# Deadtime_logic.net
KiCad netlist of a schematic drawn in Altium Designer
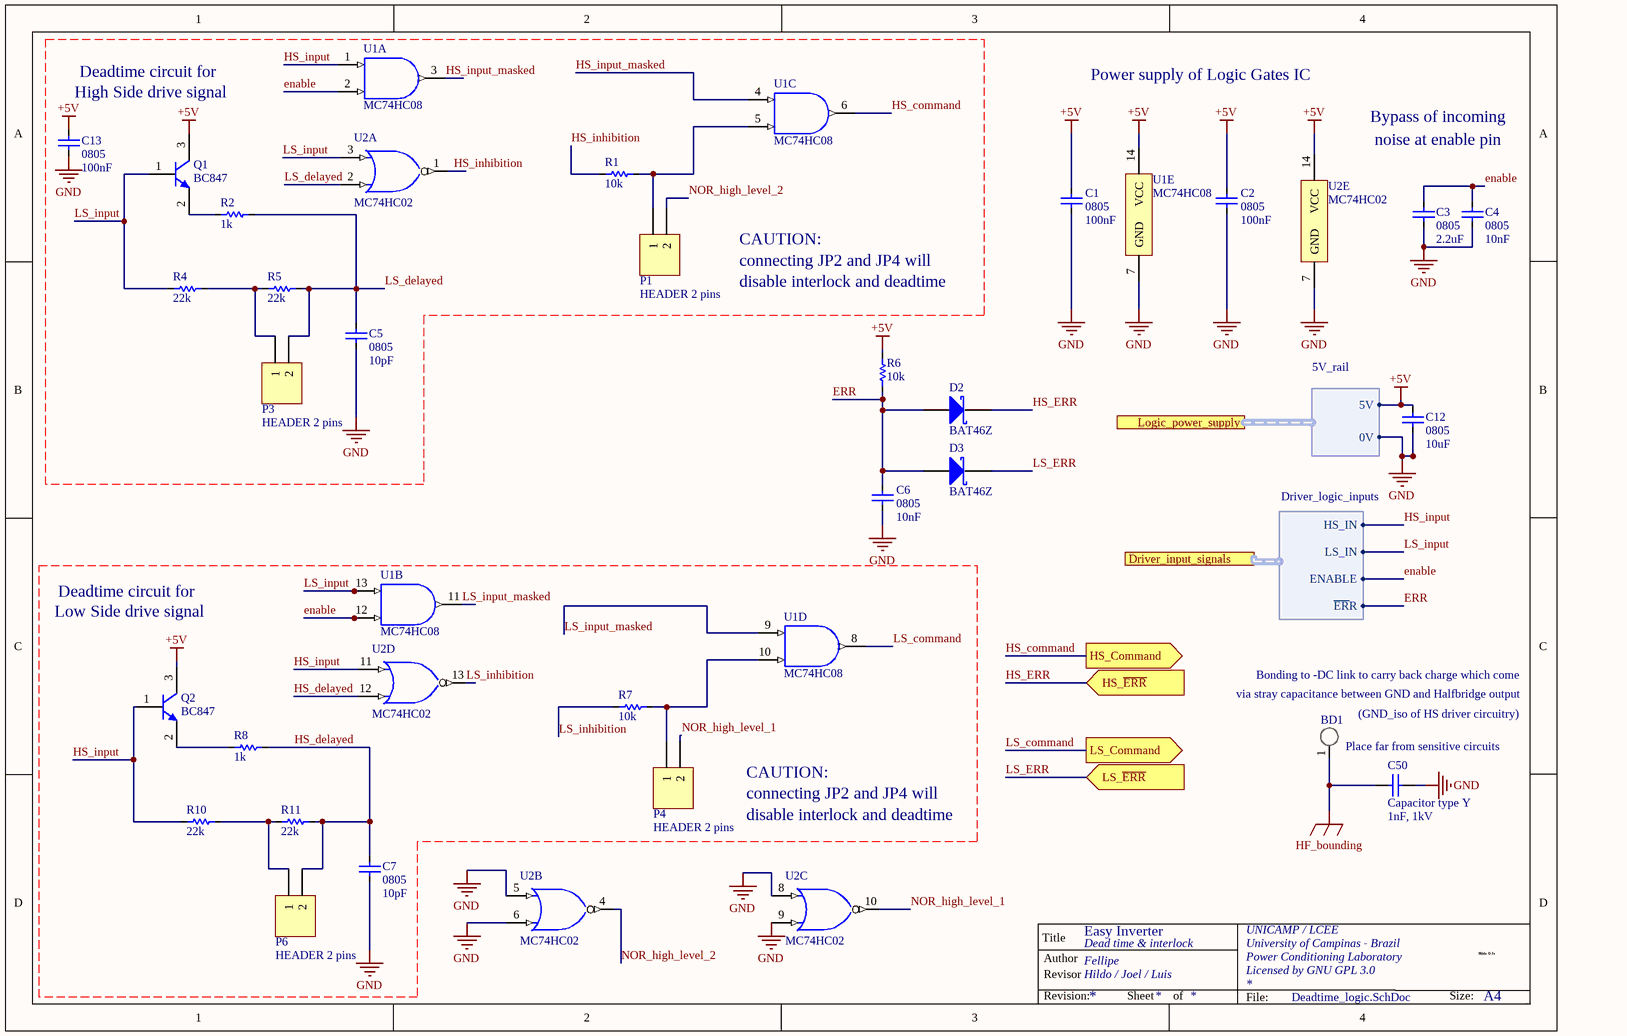
[diagram p0: Deadtime_logic.SchDoc]

(export (version "E")
  (design (tool "Eeschema 10.0.6"))
  (components
    (comp (ref "BD1")
      (value "Place far from sensitive circuits")
      (footprint "Bonding_pad")
      (libsource (lib "EdgeInverter_library") (part "Bonding_pad"))
    )
    (comp (ref "C1")
      (value "0805")
      (footprint "Capacitor 0805")
      (description "SMD ceramic capacitor 0805")
      (fields (field (name "ALTIUM_VALUE") "100nF"))
      (libsource (lib "EdgeInverter_library") (part "Capacitor 0805"))
    )
    (comp (ref "C2")
      (value "0805")
      (footprint "Capacitor 0805")
      (description "SMD ceramic capacitor 0805")
      (fields (field (name "ALTIUM_VALUE") "100nF"))
      (libsource (lib "EdgeInverter_library") (part "Capacitor 0805"))
    )
    (comp (ref "C3")
      (value "0805")
      (footprint "Capacitor 0805")
      (description "SMD ceramic capacitor 0805")
      (fields (field (name "ALTIUM_VALUE") "2.2uF"))
      (libsource (lib "EdgeInverter_library") (part "Capacitor 0805"))
    )
    (comp (ref "C4")
      (value "0805")
      (footprint "Capacitor 0805")
      (description "SMD ceramic capacitor 0805")
      (fields (field (name "ALTIUM_VALUE") "10nF"))
      (libsource (lib "EdgeInverter_library") (part "Capacitor 0805"))
    )
    (comp (ref "C5")
      (value "0805")
      (footprint "Capacitor 0805")
      (description "SMD ceramic capacitor 0805")
      (fields (field (name "ALTIUM_VALUE") "10pF"))
      (libsource (lib "EdgeInverter_library") (part "Capacitor 0805"))
    )
    (comp (ref "C6")
      (value "0805")
      (footprint "Capacitor 0805")
      (description "SMD ceramic capacitor 0805")
      (fields (field (name "ALTIUM_VALUE") "10nF"))
      (libsource (lib "EdgeInverter_library") (part "Capacitor 0805"))
    )
    (comp (ref "C7")
      (value "0805")
      (footprint "Capacitor 0805")
      (description "SMD ceramic capacitor 0805")
      (fields (field (name "ALTIUM_VALUE") "10pF"))
      (libsource (lib "EdgeInverter_library") (part "Capacitor 0805"))
    )
    (comp (ref "C12")
      (value "0805")
      (footprint "Capacitor 0805")
      (description "SMD ceramic capacitor 0805")
      (fields (field (name "ALTIUM_VALUE") "10uF"))
      (libsource (lib "EdgeInverter_library") (part "Capacitor 0805"))
    )
    (comp (ref "C13")
      (value "0805")
      (footprint "Capacitor 0805")
      (description "SMD ceramic capacitor 0805")
      (fields (field (name "ALTIUM_VALUE") "100nF"))
      (libsource (lib "EdgeInverter_library") (part "Capacitor 0805"))
    )
    (comp (ref "C50")
      (value "Capacitor type Y")
      (footprint "CAPACITOR 1812")
      (description "High Voltage Capacitor to filter EMC from heatsink")
      (fields (field (name "ALTIUM_VALUE") "1nF, 1kV"))
      (libsource (lib "EdgeInverter_library") (part "Y Capacitor"))
    )
    (comp (ref "D2")
      (value "BAT46Z")
      (footprint "SOD 123")
      (description "DIODE SCHOTTKY 100V 150MA SOD123")
      (libsource (lib "EdgeInverter_library") (part "BAT46Z"))
    )
    (comp (ref "D3")
      (value "BAT46Z")
      (footprint "SOD 123")
      (description "DIODE SCHOTTKY 100V 150MA SOD123")
      (libsource (lib "EdgeInverter_library") (part "BAT46Z"))
    )
    (comp (ref "P1")
      (value "HEADER 2 pins")
      (footprint "HDR1X2 - Jumper")
      (description "Header 2.54mm 2 pins")
      (libsource (lib "EdgeInverter_library") (part "HEADER 2 pins"))
    )
    (comp (ref "P3")
      (value "HEADER 2 pins")
      (footprint "HDR1X2 - Jumper")
      (description "Header 2.54mm 2 pins")
      (libsource (lib "EdgeInverter_library") (part "HEADER 2 pins"))
    )
    (comp (ref "P4")
      (value "HEADER 2 pins")
      (footprint "HDR1X2 - Jumper")
      (description "Header 2.54mm 2 pins")
      (libsource (lib "EdgeInverter_library") (part "HEADER 2 pins"))
    )
    (comp (ref "P6")
      (value "HEADER 2 pins")
      (footprint "HDR1X2 - Jumper")
      (description "Header 2.54mm 2 pins")
      (libsource (lib "EdgeInverter_library") (part "HEADER 2 pins"))
    )
    (comp (ref "Q1")
      (value "BC847")
      (footprint "SOT 23")
      (description "General Purpose Transistor, NPN Silicon, 3-Pin SOT-23, Pb-Free, Tape and Reel")
      (libsource (lib "EdgeInverter_library") (part "BC847BLT1G"))
    )
    (comp (ref "Q2")
      (value "BC847")
      (footprint "SOT 23")
      (description "General Purpose Transistor, NPN Silicon, 3-Pin SOT-23, Pb-Free, Tape and Reel")
      (libsource (lib "EdgeInverter_library") (part "BC847BLT1G"))
    )
    (comp (ref "R1")
      (value "10k")
      (footprint "Resistor 0805")
      (description "SMD resistor 0805")
      (fields (field (name "Comment") "Resistor 0805"))
      (libsource (lib "EdgeInverter_library") (part "Resistor 0805"))
    )
    (comp (ref "R2")
      (value "1k")
      (footprint "Resistor 0805")
      (description "SMD resistor 0805")
      (fields (field (name "Comment") "Resistor 0805"))
      (libsource (lib "EdgeInverter_library") (part "Resistor 0805"))
    )
    (comp (ref "R4")
      (value "22k")
      (footprint "Resistor 0805")
      (description "SMD resistor 0805")
      (fields (field (name "Comment") "Resistor 0805"))
      (libsource (lib "EdgeInverter_library") (part "Resistor 0805"))
    )
    (comp (ref "R5")
      (value "22k")
      (footprint "Resistor 0805")
      (description "SMD resistor 0805")
      (fields (field (name "Comment") "Resistor 0805"))
      (libsource (lib "EdgeInverter_library") (part "Resistor 0805"))
    )
    (comp (ref "R6")
      (value "10k")
      (footprint "Resistor 0805")
      (description "SMD resistor 0805")
      (fields (field (name "Comment") "Resistor 0805"))
      (libsource (lib "EdgeInverter_library") (part "Resistor 0805"))
    )
    (comp (ref "R7")
      (value "10k")
      (footprint "Resistor 0805")
      (description "SMD resistor 0805")
      (fields (field (name "Comment") "Resistor 0805"))
      (libsource (lib "EdgeInverter_library") (part "Resistor 0805"))
    )
    (comp (ref "R8")
      (value "1k")
      (footprint "Resistor 0805")
      (description "SMD resistor 0805")
      (fields (field (name "Comment") "Resistor 0805"))
      (libsource (lib "EdgeInverter_library") (part "Resistor 0805"))
    )
    (comp (ref "R10")
      (value "22k")
      (footprint "Resistor 0805")
      (description "SMD resistor 0805")
      (fields (field (name "Comment") "Resistor 0805"))
      (libsource (lib "EdgeInverter_library") (part "Resistor 0805"))
    )
    (comp (ref "R11")
      (value "22k")
      (footprint "Resistor 0805")
      (description "SMD resistor 0805")
      (fields (field (name "Comment") "Resistor 0805"))
      (libsource (lib "EdgeInverter_library") (part "Resistor 0805"))
    )
    (comp (ref "U1")
      (value "MC74HC08")
      (footprint "SOIC 14")
      (description "Quadruple 2-Input Positive-AND Gates")
      (fields (field (name "Comment") "MC74HC08ADG"))
      (libsource (lib "") (part "MC74HC08ADG_2"))
    )
    (comp (ref "U2")
      (value "MC74HC02")
      (footprint "SOIC 14")
      (description "Logic Quad 2-Input NOR Gates")
      (fields (field (name "Comment") "MC74HC02ADG"))
      (libsource (lib "") (part "MC74HC02ADG_2"))
    )
  )
  (nets
    (net (code "3") (name "+5V") (class "Default")
      (node (ref "C1") (pin "1") (pinfunction "1_1") (pintype "passive"))
      (node (ref "C12") (pin "1") (pinfunction "1_1") (pintype "passive"))
      (node (ref "C13") (pin "1") (pinfunction "1_1") (pintype "passive"))
      (node (ref "C2") (pin "1") (pinfunction "1_1") (pintype "passive"))
      (node (ref "Q1") (pin "3") (pinfunction "C_3") (pintype "passive"))
      (node (ref "Q2") (pin "3") (pinfunction "C_3") (pintype "passive"))
      (node (ref "R6") (pin "2") (pinfunction "2_2") (pintype "passive"))
      (node (ref "U1") (pin "14") (pinfunction "VCC_14") (pintype "power_in"))
      (node (ref "U2") (pin "14") (pinfunction "VCC_14") (pintype "power_in"))
    )
    (net (code "4") (name "/ERR") (class "Default")
      (node (ref "C6") (pin "1") (pinfunction "1_1") (pintype "passive"))
      (node (ref "D2") (pin "1") (pinfunction "A_1") (pintype "passive"))
      (node (ref "D3") (pin "1") (pinfunction "A_1") (pintype "passive"))
      (node (ref "R6") (pin "1") (pinfunction "1_1") (pintype "passive"))
    )
    (net (code "5") (name "/HS_ERR") (class "Default")
      (node (ref "D2") (pin "2") (pinfunction "K_2") (pintype "passive"))
    )
    (net (code "6") (name "/HS_command") (class "Default")
      (node (ref "U1") (pin "6") (pinfunction "2Y_6") (pintype "output"))
    )
    (net (code "7") (name "/HS_delayed") (class "Default")
      (node (ref "C7") (pin "1") (pinfunction "1_1") (pintype "passive"))
      (node (ref "P6") (pin "2") (pinfunction "2_2") (pintype "passive"))
      (node (ref "R11") (pin "2") (pinfunction "2_2") (pintype "passive"))
      (node (ref "R8") (pin "2") (pinfunction "2_2") (pintype "passive"))
      (node (ref "U2") (pin "12") (pinfunction "4B_12") (pintype "input"))
    )
    (net (code "8") (name "/HS_inhibition") (class "Default")
      (node (ref "R1") (pin "1") (pinfunction "1_1") (pintype "passive"))
      (node (ref "U2") (pin "1") (pinfunction "1Y_1") (pintype "output"))
    )
    (net (code "9") (name "/HS_input") (class "Default")
      (node (ref "Q2") (pin "1") (pinfunction "B_1") (pintype "passive"))
      (node (ref "R10") (pin "1") (pinfunction "1_1") (pintype "passive"))
      (node (ref "U1") (pin "1") (pinfunction "1A_1") (pintype "input"))
      (node (ref "U2") (pin "11") (pinfunction "4A_11") (pintype "input"))
    )
    (net (code "10") (name "/HS_input_masked") (class "Default")
      (node (ref "U1") (pin "3") (pinfunction "1Y_3") (pintype "output"))
      (node (ref "U1") (pin "4") (pinfunction "2A_4") (pintype "input"))
    )
    (net (code "11") (name "/LS_ERR") (class "Default")
      (node (ref "D3") (pin "2") (pinfunction "K_2") (pintype "passive"))
    )
    (net (code "12") (name "/LS_command") (class "Default")
      (node (ref "U1") (pin "8") (pinfunction "3Y_8") (pintype "output"))
    )
    (net (code "13") (name "/LS_delayed") (class "Default")
      (node (ref "C5") (pin "1") (pinfunction "1_1") (pintype "passive"))
      (node (ref "P3") (pin "2") (pinfunction "2_2") (pintype "passive"))
      (node (ref "R2") (pin "2") (pinfunction "2_2") (pintype "passive"))
      (node (ref "R5") (pin "2") (pinfunction "2_2") (pintype "passive"))
      (node (ref "U2") (pin "2") (pinfunction "1A_2") (pintype "input"))
    )
    (net (code "14") (name "/LS_inhibition") (class "Default")
      (node (ref "R7") (pin "1") (pinfunction "1_1") (pintype "passive"))
      (node (ref "U2") (pin "13") (pinfunction "4Y_13") (pintype "output"))
    )
    (net (code "15") (name "/LS_input") (class "Default")
      (node (ref "Q1") (pin "1") (pinfunction "B_1") (pintype "passive"))
      (node (ref "R4") (pin "1") (pinfunction "1_1") (pintype "passive"))
      (node (ref "U1") (pin "13") (pinfunction "4B_13") (pintype "input"))
      (node (ref "U2") (pin "3") (pinfunction "1B_3") (pintype "input"))
    )
    (net (code "16") (name "/LS_input_masked") (class "Default")
      (node (ref "U1") (pin "11") (pinfunction "4Y_11") (pintype "output"))
      (node (ref "U1") (pin "9") (pinfunction "3A_9") (pintype "input"))
    )
    (net (code "17") (name "/NOR_high_level_1") (class "Default")
      (node (ref "P4") (pin "2") (pinfunction "2_2") (pintype "passive"))
      (node (ref "U2") (pin "10") (pinfunction "3Y_10") (pintype "output"))
    )
    (net (code "18") (name "/NOR_high_level_2") (class "Default")
      (node (ref "P1") (pin "2") (pinfunction "2_2") (pintype "passive"))
      (node (ref "U2") (pin "4") (pinfunction "2Y_4") (pintype "output"))
    )
    (net (code "19") (name "/enable") (class "Default")
      (node (ref "C3") (pin "1") (pinfunction "1_1") (pintype "passive"))
      (node (ref "C4") (pin "1") (pinfunction "1_1") (pintype "passive"))
      (node (ref "U1") (pin "12") (pinfunction "4A_12") (pintype "input"))
      (node (ref "U1") (pin "2") (pinfunction "1B_2") (pintype "input"))
    )
    (net (code "22") (name "GND") (class "Default")
      (node (ref "C1") (pin "2") (pinfunction "2_2") (pintype "passive"))
      (node (ref "C12") (pin "2") (pinfunction "2_2") (pintype "passive"))
      (node (ref "C13") (pin "2") (pinfunction "2_2") (pintype "passive"))
      (node (ref "C2") (pin "2") (pinfunction "2_2") (pintype "passive"))
      (node (ref "C3") (pin "2") (pinfunction "2_2") (pintype "passive"))
      (node (ref "C4") (pin "2") (pinfunction "2_2") (pintype "passive"))
      (node (ref "C5") (pin "2") (pinfunction "2_2") (pintype "passive"))
      (node (ref "C50") (pin "2") (pinfunction "2_2") (pintype "passive"))
      (node (ref "C6") (pin "2") (pinfunction "2_2") (pintype "passive"))
      (node (ref "C7") (pin "2") (pinfunction "2_2") (pintype "passive"))
      (node (ref "U1") (pin "7") (pinfunction "GND_7") (pintype "power_in"))
      (node (ref "U2") (pin "5") (pinfunction "2A_5") (pintype "input"))
      (node (ref "U2") (pin "6") (pinfunction "2B_6") (pintype "input"))
      (node (ref "U2") (pin "7") (pinfunction "GND_7") (pintype "power_in"))
      (node (ref "U2") (pin "8") (pinfunction "3A_8") (pintype "input"))
      (node (ref "U2") (pin "9") (pinfunction "3B_9") (pintype "input"))
    )
    (net (code "23") (name "HF_bounding") (class "Default")
      (node (ref "BD1") (pin "1") (pinfunction "1_1") (pintype "passive"))
      (node (ref "C50") (pin "1") (pinfunction "1_1") (pintype "passive"))
    )
    (net (code "24") (name "Net-(P3-Pad1)") (class "Default")
      (node (ref "P3") (pin "1") (pinfunction "1_1") (pintype "passive"))
      (node (ref "R4") (pin "2") (pinfunction "2_2") (pintype "passive"))
      (node (ref "R5") (pin "1") (pinfunction "1_1") (pintype "passive"))
    )
    (net (code "25") (name "Net-(P6-Pad1)") (class "Default")
      (node (ref "P6") (pin "1") (pinfunction "1_1") (pintype "passive"))
      (node (ref "R10") (pin "2") (pinfunction "2_2") (pintype "passive"))
      (node (ref "R11") (pin "1") (pinfunction "1_1") (pintype "passive"))
    )
    (net (code "26") (name "Net-(Q1-E)") (class "Default")
      (node (ref "Q1") (pin "2") (pinfunction "E_2") (pintype "passive"))
      (node (ref "R2") (pin "1") (pinfunction "1_1") (pintype "passive"))
    )
    (net (code "27") (name "Net-(Q2-E)") (class "Default")
      (node (ref "Q2") (pin "2") (pinfunction "E_2") (pintype "passive"))
      (node (ref "R8") (pin "1") (pinfunction "1_1") (pintype "passive"))
    )
    (net (code "28") (name "Net-(U1C-2B)") (class "Default")
      (node (ref "P1") (pin "1") (pinfunction "1_1") (pintype "passive"))
      (node (ref "R1") (pin "2") (pinfunction "2_2") (pintype "passive"))
      (node (ref "U1") (pin "5") (pinfunction "2B_5") (pintype "input"))
    )
    (net (code "29") (name "Net-(U1D-3B)") (class "Default")
      (node (ref "P4") (pin "1") (pinfunction "1_1") (pintype "passive"))
      (node (ref "R7") (pin "2") (pinfunction "2_2") (pintype "passive"))
      (node (ref "U1") (pin "10") (pinfunction "3B_10") (pintype "input"))
    )
  )
)
